# bread_board.net
KiCad netlist of a schematic drawn in EAGLE
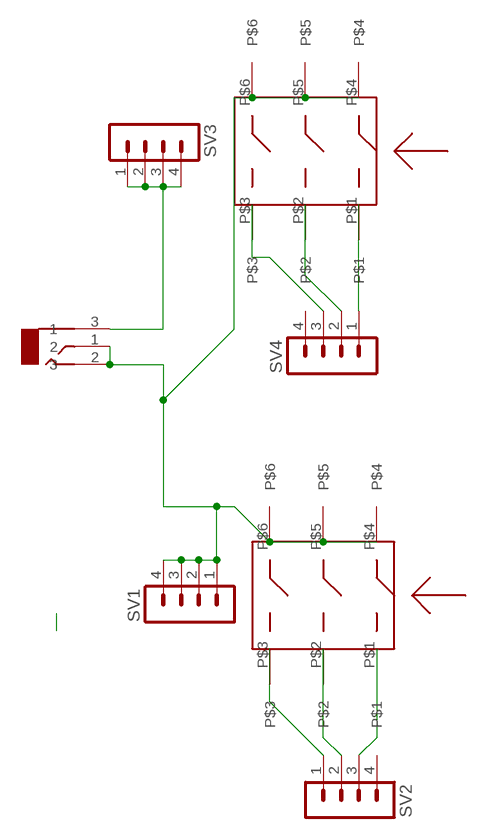
[diagram p0: schematic, sheet 1]

(export (version "E")
  (design (tool "Eeschema 10.0.6"))
  (components
    (comp (ref "J2")
      (value "DC_JACK")
      (footprint "eagle-import:DC_JACK")
      (libsource (lib "eagle-import") (part "DC_JACK"))
    )
    (comp (ref "SV1")
      (value "MA04-1")
      (footprint "eagle-import:MA04-1")
      (libsource (lib "eagle-import") (part "MA04-1"))
    )
    (comp (ref "SV2")
      (value "MA04-1")
      (footprint "eagle-import:MA04-1")
      (libsource (lib "eagle-import") (part "MA04-1"))
    )
    (comp (ref "SV3")
      (value "MA04-1")
      (footprint "eagle-import:MA04-1")
      (libsource (lib "eagle-import") (part "MA04-1"))
    )
    (comp (ref "SV4")
      (value "MA04-1")
      (footprint "eagle-import:MA04-1")
      (libsource (lib "eagle-import") (part "MA04-1"))
    )
    (comp (ref "U$1")
      (value "AUDIO_JACK")
      (footprint "eagle-import:AUDIO_JACK")
      (libsource (lib "eagle-import") (part "AUDIO_JACK"))
    )
    (comp (ref "U$2")
      (value "AUDIO_JACK")
      (footprint "eagle-import:AUDIO_JACK")
      (libsource (lib "eagle-import") (part "AUDIO_JACK"))
    )
  )
  (nets
    (net (code "1") (name "/GND") (class "Default")
      (node (ref "J2") (pin "1") (pinfunction "2_1") (pintype "bidirectional"))
      (node (ref "J2") (pin "2") (pinfunction "3_2") (pintype "bidirectional"))
      (node (ref "SV1") (pin "1") (pinfunction "1_1") (pintype "passive"))
      (node (ref "SV1") (pin "2") (pinfunction "2_2") (pintype "passive"))
      (node (ref "SV1") (pin "3") (pinfunction "3_3") (pintype "passive"))
      (node (ref "SV1") (pin "4") (pinfunction "4_4") (pintype "passive"))
      (node (ref "U$1") (pin "P$4") (pinfunction "P$4_P$4") (pintype "bidirectional"))
      (node (ref "U$1") (pin "P$5") (pinfunction "P$5_P$5") (pintype "bidirectional"))
      (node (ref "U$1") (pin "P$6") (pinfunction "P$6_P$6") (pintype "bidirectional"))
      (node (ref "U$2") (pin "P$4") (pinfunction "P$4_P$4") (pintype "bidirectional"))
      (node (ref "U$2") (pin "P$5") (pinfunction "P$5_P$5") (pintype "bidirectional"))
      (node (ref "U$2") (pin "P$6") (pinfunction "P$6_P$6") (pintype "bidirectional"))
    )
    (net (code "2") (name "Net-(J2-1)") (class "Default")
      (node (ref "J2") (pin "3") (pinfunction "1_3") (pintype "bidirectional"))
      (node (ref "SV3") (pin "1") (pinfunction "1_1") (pintype "passive"))
      (node (ref "SV3") (pin "2") (pinfunction "2_2") (pintype "passive"))
      (node (ref "SV3") (pin "3") (pinfunction "3_3") (pintype "passive"))
      (node (ref "SV3") (pin "4") (pinfunction "4_4") (pintype "passive"))
    )
    (net (code "3") (name "Net-(SV2-Pad1)") (class "Default")
      (node (ref "SV2") (pin "1") (pinfunction "1_1") (pintype "passive"))
      (node (ref "U$2") (pin "P$3") (pinfunction "P$3_P$3") (pintype "bidirectional"))
    )
    (net (code "4") (name "Net-(SV2-Pad2)") (class "Default")
      (node (ref "SV2") (pin "2") (pinfunction "2_2") (pintype "passive"))
      (node (ref "U$2") (pin "P$2") (pinfunction "P$2_P$2") (pintype "bidirectional"))
    )
    (net (code "5") (name "Net-(SV2-Pad3)") (class "Default")
      (node (ref "SV2") (pin "3") (pinfunction "3_3") (pintype "passive"))
      (node (ref "U$2") (pin "P$1") (pinfunction "P$1_P$1") (pintype "bidirectional"))
    )
    (net (code "6") (name "Net-(SV4-Pad1)") (class "Default")
      (node (ref "SV4") (pin "1") (pinfunction "1_1") (pintype "passive"))
      (node (ref "U$1") (pin "P$1") (pinfunction "P$1_P$1") (pintype "bidirectional"))
    )
    (net (code "7") (name "Net-(SV4-Pad2)") (class "Default")
      (node (ref "SV4") (pin "2") (pinfunction "2_2") (pintype "passive"))
      (node (ref "U$1") (pin "P$2") (pinfunction "P$2_P$2") (pintype "bidirectional"))
    )
    (net (code "8") (name "Net-(SV4-Pad3)") (class "Default")
      (node (ref "SV4") (pin "3") (pinfunction "3_3") (pintype "passive"))
      (node (ref "U$1") (pin "P$3") (pinfunction "P$3_P$3") (pintype "bidirectional"))
    )
    (net (code "9") (name "unconnected-(SV2-Pad4)") (class "Default")
      (node (ref "SV2") (pin "4") (pinfunction "4_4") (pintype "passive"))
    )
    (net (code "10") (name "unconnected-(SV4-Pad4)") (class "Default")
      (node (ref "SV4") (pin "4") (pinfunction "4_4") (pintype "passive"))
    )
  )
)
